# CNYboard.net
KiCad netlist of a schematic drawn in EAGLE
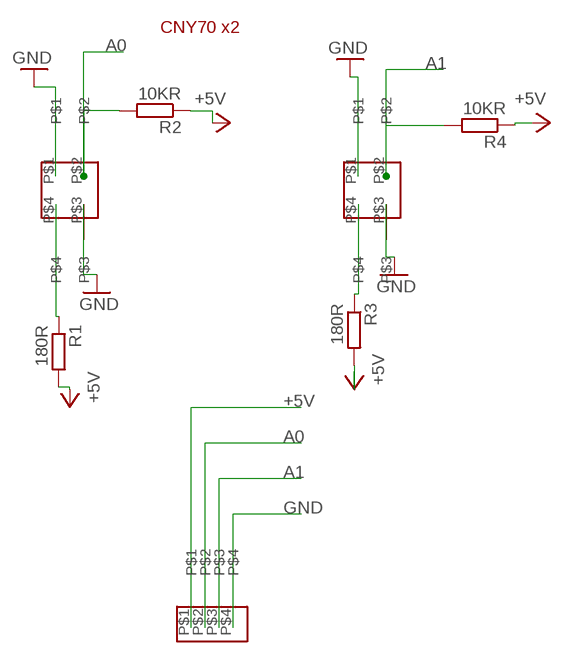
[diagram p0: schematic, sheet 1]

(export (version "E")
  (design (tool "Eeschema 10.0.6"))
  (components
    (comp (ref "R1")
      (value "180R")
      (footprint "eagle-import:R0603")
      (libsource (lib "eagle-import") (part "R-EU_R0603"))
    )
    (comp (ref "R2")
      (value "10KR")
      (footprint "eagle-import:R0603")
      (libsource (lib "eagle-import") (part "R-EU_R0603"))
    )
    (comp (ref "R3")
      (value "180R")
      (footprint "eagle-import:R0603")
      (libsource (lib "eagle-import") (part "R-EU_R0603"))
    )
    (comp (ref "R4")
      (value "10KR")
      (footprint "eagle-import:R0603")
      (libsource (lib "eagle-import") (part "R-EU_R0603"))
    )
    (comp (ref "U$1")
      (value "CNYSOKET")
      (footprint "eagle-import:CNYSOKET")
      (libsource (lib "eagle-import") (part "CNYSOKET"))
    )
    (comp (ref "U$2")
      (value "CNYSOKET")
      (footprint "eagle-import:CNYSOKET")
      (libsource (lib "eagle-import") (part "CNYSOKET"))
    )
    (comp (ref "U$3")
      (value "PIN4")
      (footprint "eagle-import:PIN4")
      (libsource (lib "eagle-import") (part "PIN4"))
    )
  )
  (nets
    (net (code "1") (name "+5V") (class "Default")
      (node (ref "R1") (pin "2") (pinfunction "2_2") (pintype "passive"))
      (node (ref "R2") (pin "1") (pinfunction "1_1") (pintype "passive"))
      (node (ref "R3") (pin "2") (pinfunction "2_2") (pintype "passive"))
      (node (ref "R4") (pin "1") (pinfunction "1_1") (pintype "passive"))
      (node (ref "U$3") (pin "P$1") (pinfunction "P$1_P$1") (pintype "bidirectional"))
    )
    (net (code "2") (name "/A0") (class "Default")
      (node (ref "R2") (pin "2") (pinfunction "2_2") (pintype "passive"))
      (node (ref "U$1") (pin "P$2") (pinfunction "P$2_P$2") (pintype "bidirectional"))
      (node (ref "U$3") (pin "P$2") (pinfunction "P$2_P$2") (pintype "bidirectional"))
    )
    (net (code "3") (name "/A1") (class "Default")
      (node (ref "R4") (pin "2") (pinfunction "2_2") (pintype "passive"))
      (node (ref "U$2") (pin "P$2") (pinfunction "P$2_P$2") (pintype "bidirectional"))
      (node (ref "U$3") (pin "P$3") (pinfunction "P$3_P$3") (pintype "bidirectional"))
    )
    (net (code "4") (name "GND") (class "Default")
      (node (ref "U$1") (pin "P$1") (pinfunction "P$1_P$1") (pintype "bidirectional"))
      (node (ref "U$1") (pin "P$3") (pinfunction "P$3_P$3") (pintype "bidirectional"))
      (node (ref "U$2") (pin "P$1") (pinfunction "P$1_P$1") (pintype "bidirectional"))
      (node (ref "U$2") (pin "P$3") (pinfunction "P$3_P$3") (pintype "bidirectional"))
      (node (ref "U$3") (pin "P$4") (pinfunction "P$4_P$4") (pintype "bidirectional"))
    )
    (net (code "5") (name "Net-(R1-Pad1)") (class "Default")
      (node (ref "R1") (pin "1") (pinfunction "1_1") (pintype "passive"))
      (node (ref "U$1") (pin "P$4") (pinfunction "P$4_P$4") (pintype "bidirectional"))
    )
    (net (code "6") (name "Net-(R3-Pad1)") (class "Default")
      (node (ref "R3") (pin "1") (pinfunction "1_1") (pintype "passive"))
      (node (ref "U$2") (pin "P$4") (pinfunction "P$4_P$4") (pintype "bidirectional"))
    )
  )
)
